# Sheet1.net
KiCad netlist of a schematic drawn in Altium Designer
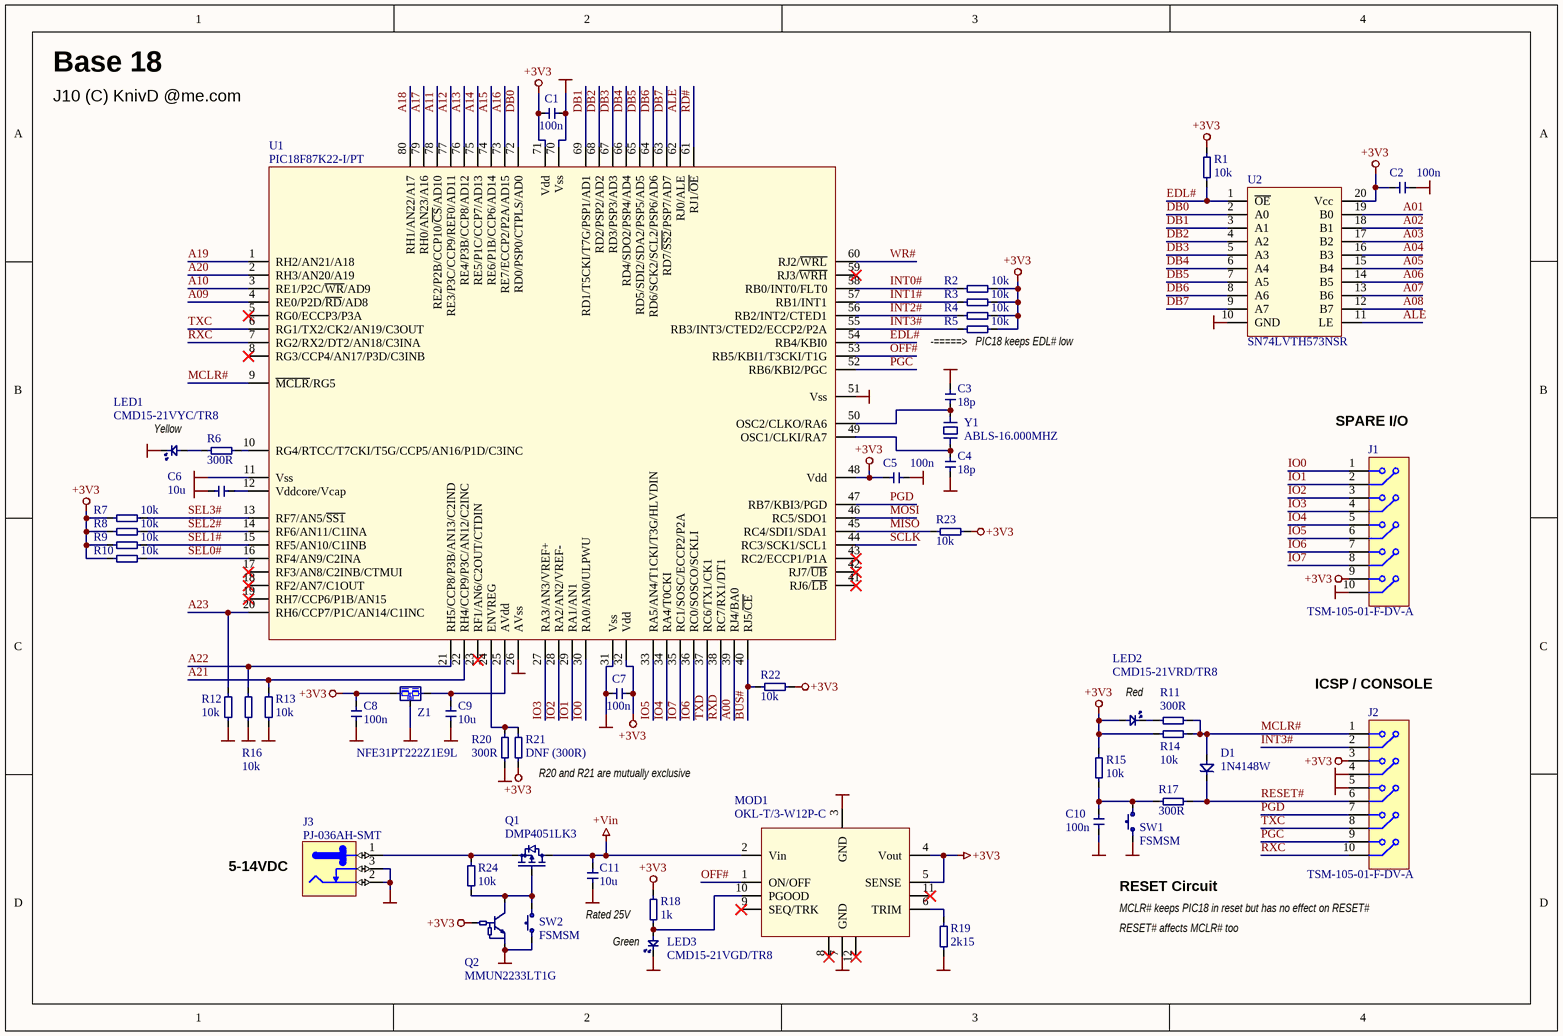
[diagram p0: Sheet1.SchDoc]

(export (version "E")
  (design (tool "Eeschema 10.0.6"))
  (components
    (comp (ref "C1")
      (value "100n")
      (footprint "CAPC3216X110N")
      (description "Capacitor")
      (libsource (lib "Discretes") (part "Capacitor"))
    )
    (comp (ref "C2")
      (value "100n")
      (footprint "CAPC3216X110N")
      (description "Capacitor")
      (libsource (lib "Discretes") (part "Capacitor"))
    )
    (comp (ref "C3")
      (value "18p")
      (footprint "CAPC3216X110N")
      (description "Capacitor")
      (libsource (lib "Discretes") (part "Capacitor"))
    )
    (comp (ref "C4")
      (value "18p")
      (footprint "CAPC3216X110N")
      (description "Capacitor")
      (libsource (lib "Discretes") (part "Capacitor"))
    )
    (comp (ref "C5")
      (value "100n")
      (footprint "CAPC3216X110N")
      (description "Capacitor")
      (libsource (lib "Discretes") (part "Capacitor"))
    )
    (comp (ref "C6")
      (value "10u")
      (footprint "CAPC3216X110N")
      (description "Capacitor")
      (libsource (lib "Discretes") (part "Capacitor"))
    )
    (comp (ref "C7")
      (value "100n")
      (footprint "CAPC3216X110N")
      (description "Capacitor")
      (libsource (lib "Discretes") (part "Capacitor"))
    )
    (comp (ref "C8")
      (value "100n")
      (footprint "CAPC3216X110N")
      (description "Capacitor")
      (libsource (lib "Discretes") (part "Capacitor"))
    )
    (comp (ref "C9")
      (value "10u")
      (footprint "CAPC3216X110N")
      (description "Capacitor")
      (libsource (lib "Discretes") (part "Capacitor"))
    )
    (comp (ref "C10")
      (value "100n")
      (footprint "CAPC3216X110N")
      (description "Capacitor")
      (libsource (lib "Discretes") (part "Capacitor"))
    )
    (comp (ref "C11")
      (value "10u/25V")
      (footprint "CAPC3216X110N")
      (description "Capacitor")
      (fields (field (name "NOTE") "10u"))
      (libsource (lib "Discretes") (part "Capacitor"))
    )
    (comp (ref "D1")
      (value "1N4148W")
      (footprint "SOD-123")
      (description "Schottky diode")
      (libsource (lib "Discretes") (part "Diode Schottky"))
    )
    (comp (ref "J1")
      (value "TSM-105-01-F-DV-A")
      (footprint "2015-2X05XD")
      (description "Dual row, 10-way connector")
      (libsource (lib "Connectors") (part "Connector 2x5"))
    )
    (comp (ref "J2")
      (value "TSM-105-01-F-DV-A")
      (footprint "2015-2X05XD")
      (description "Dual row, 10-way connector")
      (libsource (lib "Connectors") (part "Connector 2x5"))
    )
    (comp (ref "J3")
      (value "PJ-036AH-SMT")
      (footprint "PJ-036AH-SMT")
      (description "2.1/5.5mm barrel power jack, SMT")
      (fields (field (name "AUTHOR") "CERN DEM JLC"))
      (libsource (lib "Connectors") (part "LUMBERG_161314"))
    )
    (comp (ref "LED1")
      (value "CMD15-21VYC/TR8")
      (footprint "LED_OSRAM_LYN971")
      (description "Light Emitting Diode")
      (libsource (lib "Discretes") (part "LED"))
    )
    (comp (ref "LED2")
      (value "CMD15-21VRD/TR8")
      (footprint "LED_OSRAM_LHN974")
      (description "Light Emitting Diode")
      (libsource (lib "") (part "LED_1"))
    )
    (comp (ref "LED3")
      (value "CMD15-21VGD/TR8")
      (footprint "LED_OSRAM_LGN971")
      (description "Light Emitting Diode")
      (libsource (lib "Discretes") (part "LED"))
    )
    (comp (ref "MOD1")
      (value "OKL-T/3-W12P-C")
      (footprint "OKL-T/3-W12")
      (description "Programmable Output 3-Amp iLGA SMT PoLs")
      (fields (field (name "MANUFACTURER") "Murata"))
      (libsource (lib "Modules") (part "OKL-T/3-W12"))
    )
    (comp (ref "Q1")
      (value "DMP4051LK3")
      (footprint "TO228P991X239-3N-R546X521")
      (description "P-channel FET transistor")
      (libsource (lib "Discretes") (part "P-FET"))
    )
    (comp (ref "Q2")
      (value "MMUN2233LT1G")
      (footprint "SOT23-3")
      (description "NPN biased bipolar transistor")
      (libsource (lib "Discretes") (part "NPN BIASED"))
    )
    (comp (ref "R1")
      (value "10k")
      (footprint "RESC3216X75N")
      (description "Resistor")
      (libsource (lib "") (part "Resistor_1"))
    )
    (comp (ref "R2")
      (value "10k")
      (footprint "RESC3216X75N")
      (description "Resistor")
      (libsource (lib "") (part "Resistor_2"))
    )
    (comp (ref "R3")
      (value "10k")
      (footprint "RESC3216X75N")
      (description "Resistor")
      (libsource (lib "") (part "Resistor_2"))
    )
    (comp (ref "R4")
      (value "10k")
      (footprint "RESC3216X75N")
      (description "Resistor")
      (libsource (lib "") (part "Resistor_2"))
    )
    (comp (ref "R5")
      (value "10k")
      (footprint "RESC3216X75N")
      (description "Resistor")
      (libsource (lib "") (part "Resistor_2"))
    )
    (comp (ref "R6")
      (value "300R")
      (footprint "RESC3216X75N")
      (description "Resistor")
      (libsource (lib "") (part "Resistor_3"))
    )
    (comp (ref "R7")
      (value "10k")
      (footprint "RESC3216X75N")
      (description "Resistor")
      (libsource (lib "") (part "Resistor_1"))
    )
    (comp (ref "R8")
      (value "10k")
      (footprint "RESC3216X75N")
      (description "Resistor")
      (libsource (lib "") (part "Resistor_1"))
    )
    (comp (ref "R9")
      (value "10k")
      (footprint "RESC3216X75N")
      (description "Resistor")
      (libsource (lib "") (part "Resistor_1"))
    )
    (comp (ref "R10")
      (value "10k")
      (footprint "RESC3216X75N")
      (description "Resistor")
      (libsource (lib "") (part "Resistor_1"))
    )
    (comp (ref "R11")
      (value "300R")
      (footprint "RESC3216X75N")
      (description "Resistor")
      (libsource (lib "") (part "Resistor_2"))
    )
    (comp (ref "R12")
      (value "10k")
      (footprint "RESC3216X75N")
      (description "Resistor")
      (libsource (lib "Discretes") (part "Resistor"))
    )
    (comp (ref "R13")
      (value "10k")
      (footprint "RESC3216X75N")
      (description "Resistor")
      (libsource (lib "Discretes") (part "Resistor"))
    )
    (comp (ref "R14")
      (value "10k")
      (footprint "RESC3216X75N")
      (description "Resistor")
      (libsource (lib "") (part "Resistor_2"))
    )
    (comp (ref "R15")
      (value "10k")
      (footprint "RESC3216X75N")
      (description "Resistor")
      (libsource (lib "") (part "Resistor_1"))
    )
    (comp (ref "R16")
      (value "10k")
      (footprint "RESC3216X75N")
      (description "Resistor")
      (libsource (lib "Discretes") (part "Resistor"))
    )
    (comp (ref "R17")
      (value "300R")
      (footprint "RESC3216X75N")
      (description "Resistor")
      (libsource (lib "") (part "Resistor_3"))
    )
    (comp (ref "R18")
      (value "1k")
      (footprint "RESC3216X75N")
      (description "Resistor")
      (libsource (lib "Discretes") (part "Resistor"))
    )
    (comp (ref "R19")
      (value "2k15")
      (footprint "RESC3216X75N")
      (description "Resistor")
      (libsource (lib "") (part "Resistor_1"))
    )
    (comp (ref "R20")
      (value "300R")
      (footprint "RESC3216X75N")
      (description "Resistor")
      (libsource (lib "Discretes") (part "Resistor"))
    )
    (comp (ref "R21")
      (value "DNF (300R)")
      (footprint "RESC3216X75N")
      (description "Resistor")
      (libsource (lib "Discretes") (part "Resistor"))
    )
    (comp (ref "R22")
      (value "10k")
      (footprint "RESC3216X75N")
      (description "Resistor")
      (libsource (lib "") (part "Resistor_2"))
    )
    (comp (ref "R23")
      (value "10k")
      (footprint "RESC3216X75N")
      (description "Resistor")
      (libsource (lib "") (part "Resistor_2"))
    )
    (comp (ref "R24")
      (value "10k")
      (footprint "RESC3216X75N")
      (description "Resistor")
      (libsource (lib "") (part "Resistor_1"))
    )
    (comp (ref "SW1")
      (value "FSMSM")
      (footprint "PB_TYCO_FSMSM")
      (description "Switch, Momentary, Normal Open")
      (libsource (lib "Switches") (part "Switch MNO SPST"))
    )
    (comp (ref "SW2")
      (value "FSMSM")
      (footprint "PB_TYCO_FSMSM")
      (description "Switch, Momentary, Normal Open")
      (libsource (lib "Switches") (part "Switch MNO SPST"))
    )
    (comp (ref "U1")
      (value "PIC18F87K22-I/PT")
      (footprint "QFP50P1400X1400X120-80N")
      (description "High-Performance, 1-Mbit Enhanced Flash MCUs  with 12-Bit A/D and XLP Technology")
      (fields (field (name "MANUFACTURER") "Microchip"))
      (libsource (lib "IC Microcontrollers and Processors") (part "PIC18F87K22"))
    )
    (comp (ref "U2")
      (value "SN74LVTH573NSR")
      (footprint "SOIC127P780X200-20N")
      (description "A Octal Transparent D-Type Latches With 3-State Outputs")
      (libsource (lib "IC Logic") (part "74xxx373"))
    )
    (comp (ref "Y1")
      (value "ABLS-16.000MHZ")
      (footprint "XTAL1140X470X160N")
      (description "Crystal Resonator")
      (libsource (lib "Discretes") (part "Crystal"))
    )
    (comp (ref "Z1")
      (value "NFE31PT222Z1E9L")
      (footprint "NFE31xx")
      (description "Hybrid filter")
      (libsource (lib "Misc") (part "Filter"))
    )
  )
  (nets
    (net (code "1") (name "+3V3") (class "Default")
      (node (ref "C1") (pin "1") (pintype "passive"))
      (node (ref "C2") (pin "1") (pintype "passive"))
      (node (ref "C5") (pin "1") (pintype "passive"))
      (node (ref "C7") (pin "1") (pintype "passive"))
      (node (ref "C8") (pin "1") (pintype "passive"))
      (node (ref "J1") (pin "9") (pinfunction "9_9") (pintype "passive"))
      (node (ref "J2") (pin "3") (pinfunction "3_3") (pintype "passive"))
      (node (ref "LED2") (pin "2") (pintype "passive"))
      (node (ref "MOD1") (pin "4") (pinfunction "Vout_4") (pintype "passive"))
      (node (ref "MOD1") (pin "5") (pinfunction "SENSE_5") (pintype "passive"))
      (node (ref "Q2") (pin "1") (pinfunction "B_1") (pintype "passive"))
      (node (ref "R1") (pin "2") (pintype "passive"))
      (node (ref "R10") (pin "1") (pintype "passive"))
      (node (ref "R14") (pin "2") (pintype "passive"))
      (node (ref "R15") (pin "2") (pintype "passive"))
      (node (ref "R18") (pin "1") (pintype "passive"))
      (node (ref "R2") (pin "1") (pintype "passive"))
      (node (ref "R21") (pin "2") (pintype "passive"))
      (node (ref "R22") (pin "1") (pintype "passive"))
      (node (ref "R23") (pin "1") (pintype "passive"))
      (node (ref "R3") (pin "1") (pintype "passive"))
      (node (ref "R4") (pin "1") (pintype "passive"))
      (node (ref "R5") (pin "1") (pintype "passive"))
      (node (ref "R7") (pin "1") (pintype "passive"))
      (node (ref "R8") (pin "1") (pintype "passive"))
      (node (ref "R9") (pin "1") (pintype "passive"))
      (node (ref "U1") (pin "32") (pinfunction "Vdd_32") (pintype "passive"))
      (node (ref "U1") (pin "48") (pinfunction "Vdd_48") (pintype "passive"))
      (node (ref "U1") (pin "71") (pinfunction "Vdd_71") (pintype "passive"))
      (node (ref "U2") (pin "20") (pinfunction "Vcc_20") (pintype "passive"))
      (node (ref "Z1") (pin "1") (pintype "passive"))
    )
    (net (code "2") (name "+Vin") (class "Default")
      (node (ref "C11") (pin "1") (pintype "passive"))
      (node (ref "MOD1") (pin "2") (pinfunction "Vin_2") (pintype "passive"))
      (node (ref "Q1") (pin "3") (pinfunction "D_3") (pintype "passive"))
    )
    (net (code "3") (name "/A00") (class "Default")
      (node (ref "U1") (pin "39") (pinfunction "RJ4/BA0_39") (pintype "passive"))
    )
    (net (code "4") (name "/A01") (class "Default")
      (node (ref "U2") (pin "19") (pinfunction "B0_19") (pintype "passive"))
    )
    (net (code "5") (name "/A02") (class "Default")
      (node (ref "U2") (pin "18") (pinfunction "B1_18") (pintype "passive"))
    )
    (net (code "6") (name "/A03") (class "Default")
      (node (ref "U2") (pin "17") (pinfunction "B2_17") (pintype "passive"))
    )
    (net (code "7") (name "/A04") (class "Default")
      (node (ref "U2") (pin "16") (pinfunction "B3_16") (pintype "passive"))
    )
    (net (code "8") (name "/A05") (class "Default")
      (node (ref "U2") (pin "15") (pinfunction "B4_15") (pintype "passive"))
    )
    (net (code "9") (name "/A06") (class "Default")
      (node (ref "U2") (pin "14") (pinfunction "B5_14") (pintype "passive"))
    )
    (net (code "10") (name "/A07") (class "Default")
      (node (ref "U2") (pin "13") (pinfunction "B6_13") (pintype "passive"))
    )
    (net (code "11") (name "/A08") (class "Default")
      (node (ref "U2") (pin "12") (pinfunction "B7_12") (pintype "passive"))
    )
    (net (code "12") (name "/A09") (class "Default")
      (node (ref "U1") (pin "4") (pinfunction "RE0/P2D/~{RD}/AD8_4") (pintype "passive"))
    )
    (net (code "13") (name "/A10") (class "Default")
      (node (ref "U1") (pin "3") (pinfunction "RE1/P2C/~{WR}/AD9_3") (pintype "passive"))
    )
    (net (code "14") (name "/A11") (class "Default")
      (node (ref "U1") (pin "78") (pinfunction "RE2/P2B/CCP10/~{CS}/AD10_78") (pintype "passive"))
    )
    (net (code "15") (name "/A12") (class "Default")
      (node (ref "U1") (pin "77") (pinfunction "RE3/P3C/CCP9/REF0/AD11_77") (pintype "passive"))
    )
    (net (code "16") (name "/A13") (class "Default")
      (node (ref "U1") (pin "76") (pinfunction "RE4/P3B/CCP8/AD12_76") (pintype "passive"))
    )
    (net (code "17") (name "/A14") (class "Default")
      (node (ref "U1") (pin "75") (pinfunction "RE5/P1C/CCP7/AD13_75") (pintype "passive"))
    )
    (net (code "18") (name "/A15") (class "Default")
      (node (ref "U1") (pin "74") (pinfunction "RE6/P1B/CCP6/AD14_74") (pintype "passive"))
    )
    (net (code "19") (name "/A16") (class "Default")
      (node (ref "U1") (pin "73") (pinfunction "RE7/ECCP2/P2A/AD15_73") (pintype "passive"))
    )
    (net (code "20") (name "/A17") (class "Default")
      (node (ref "U1") (pin "79") (pinfunction "RH0/AN23/A16_79") (pintype "passive"))
    )
    (net (code "21") (name "/A18") (class "Default")
      (node (ref "U1") (pin "80") (pinfunction "RH1/AN22/A17_80") (pintype "passive"))
    )
    (net (code "22") (name "/A19") (class "Default")
      (node (ref "U1") (pin "1") (pinfunction "RH2/AN21/A18_1") (pintype "passive"))
    )
    (net (code "23") (name "/A20") (class "Default")
      (node (ref "U1") (pin "2") (pinfunction "RH3/AN20/A19_2") (pintype "passive"))
    )
    (net (code "24") (name "/A21") (class "Default")
      (node (ref "R13") (pin "1") (pintype "passive"))
      (node (ref "U1") (pin "22") (pinfunction "RH4/CCP9/P3C/AN12/C2INC_22") (pintype "passive"))
    )
    (net (code "25") (name "/A22") (class "Default")
      (node (ref "R16") (pin "1") (pintype "passive"))
      (node (ref "U1") (pin "21") (pinfunction "RH5/CCP8/P3B/AN13/C2IND_21") (pintype "passive"))
    )
    (net (code "26") (name "/A23") (class "Default")
      (node (ref "R12") (pin "1") (pintype "passive"))
      (node (ref "U1") (pin "20") (pinfunction "RH6/CCP7/P1C/AN14/C1INC_20") (pintype "passive"))
    )
    (net (code "27") (name "/ALE") (class "Default")
      (node (ref "U1") (pin "62") (pinfunction "RJ0/ALE_62") (pintype "passive"))
      (node (ref "U2") (pin "11") (pinfunction "LE_11") (pintype "passive"))
    )
    (net (code "28") (name "/BUS#") (class "Default")
      (node (ref "R22") (pin "2") (pintype "passive"))
      (node (ref "U1") (pin "40") (pinfunction "RJ5/~{CE}_40") (pintype "passive"))
    )
    (net (code "29") (name "/DB0") (class "Default")
      (node (ref "U1") (pin "72") (pinfunction "RD0/PSP0/CTPLS/AD0_72") (pintype "passive"))
      (node (ref "U2") (pin "2") (pinfunction "A0_2") (pintype "passive"))
    )
    (net (code "30") (name "/DB1") (class "Default")
      (node (ref "U1") (pin "69") (pinfunction "RD1/T5CKI/T7G/PSP1/AD1_69") (pintype "passive"))
      (node (ref "U2") (pin "3") (pinfunction "A1_3") (pintype "passive"))
    )
    (net (code "31") (name "/DB2") (class "Default")
      (node (ref "U1") (pin "68") (pinfunction "RD2/PSP2/AD2_68") (pintype "passive"))
      (node (ref "U2") (pin "4") (pinfunction "A2_4") (pintype "passive"))
    )
    (net (code "32") (name "/DB3") (class "Default")
      (node (ref "U1") (pin "67") (pinfunction "RD3/PSP3/AD3_67") (pintype "passive"))
      (node (ref "U2") (pin "5") (pinfunction "A3_5") (pintype "passive"))
    )
    (net (code "33") (name "/DB4") (class "Default")
      (node (ref "U1") (pin "66") (pinfunction "RD4/SDO2/PSP4/AD4_66") (pintype "passive"))
      (node (ref "U2") (pin "6") (pinfunction "A4_6") (pintype "passive"))
    )
    (net (code "34") (name "/DB5") (class "Default")
      (node (ref "U1") (pin "65") (pinfunction "RD5/SDI2/SDA2/PSP5/AD5_65") (pintype "passive"))
      (node (ref "U2") (pin "7") (pinfunction "A5_7") (pintype "passive"))
    )
    (net (code "35") (name "/DB6") (class "Default")
      (node (ref "U1") (pin "64") (pinfunction "RD6/SCK2/SCL2/PSP6/AD6_64") (pintype "passive"))
      (node (ref "U2") (pin "8") (pinfunction "A6_8") (pintype "passive"))
    )
    (net (code "36") (name "/DB7") (class "Default")
      (node (ref "U1") (pin "63") (pinfunction "RD7/~{SS2}/PSP7/AD7_63") (pintype "passive"))
      (node (ref "U2") (pin "9") (pinfunction "A7_9") (pintype "passive"))
    )
    (net (code "37") (name "/EDL#") (class "Default")
      (node (ref "R1") (pin "1") (pintype "passive"))
      (node (ref "U1") (pin "54") (pinfunction "RB4/KBI0_54") (pintype "passive"))
      (node (ref "U2") (pin "1") (pinfunction "~{OE}_1") (pintype "passive"))
    )
    (net (code "38") (name "/INT0#") (class "Default")
      (node (ref "R2") (pin "2") (pintype "passive"))
      (node (ref "U1") (pin "58") (pinfunction "RB0/INT0/FLT0_58") (pintype "passive"))
    )
    (net (code "39") (name "/INT1#") (class "Default")
      (node (ref "R3") (pin "2") (pintype "passive"))
      (node (ref "U1") (pin "57") (pinfunction "RB1/INT1_57") (pintype "passive"))
    )
    (net (code "40") (name "/INT2#") (class "Default")
      (node (ref "R4") (pin "2") (pintype "passive"))
      (node (ref "U1") (pin "56") (pinfunction "RB2/INT2/CTED1_56") (pintype "passive"))
    )
    (net (code "41") (name "/INT3#") (class "Default")
      (node (ref "J2") (pin "2") (pinfunction "2_2") (pintype "passive"))
      (node (ref "R5") (pin "2") (pintype "passive"))
      (node (ref "U1") (pin "55") (pinfunction "RB3/INT3/CTED2/ECCP2/P2A_55") (pintype "passive"))
    )
    (net (code "42") (name "/IO0") (class "Default")
      (node (ref "J1") (pin "1") (pinfunction "1_1") (pintype "passive"))
      (node (ref "U1") (pin "30") (pinfunction "RA0/AN0/ULPWU_30") (pintype "passive"))
    )
    (net (code "43") (name "/IO1") (class "Default")
      (node (ref "J1") (pin "2") (pinfunction "2_2") (pintype "passive"))
      (node (ref "U1") (pin "29") (pinfunction "RA1/AN1_29") (pintype "passive"))
    )
    (net (code "44") (name "/IO2") (class "Default")
      (node (ref "J1") (pin "3") (pinfunction "3_3") (pintype "passive"))
      (node (ref "U1") (pin "28") (pinfunction "RA2/AN2/VREF-_28") (pintype "passive"))
    )
    (net (code "45") (name "/IO3") (class "Default")
      (node (ref "J1") (pin "4") (pinfunction "4_4") (pintype "passive"))
      (node (ref "U1") (pin "27") (pinfunction "RA3/AN3/VREF+_27") (pintype "passive"))
    )
    (net (code "46") (name "/IO4") (class "Default")
      (node (ref "J1") (pin "5") (pinfunction "5_5") (pintype "passive"))
      (node (ref "U1") (pin "34") (pinfunction "RA4/T0CKI_34") (pintype "passive"))
    )
    (net (code "47") (name "/IO5") (class "Default")
      (node (ref "J1") (pin "6") (pinfunction "6_6") (pintype "passive"))
      (node (ref "U1") (pin "33") (pinfunction "RA5/AN4/T1CKI/T3G/HLVDIN_33") (pintype "passive"))
    )
    (net (code "48") (name "/IO6") (class "Default")
      (node (ref "J1") (pin "7") (pinfunction "7_7") (pintype "passive"))
      (node (ref "U1") (pin "36") (pinfunction "RC0/SOSCO/SCKLI_36") (pintype "passive"))
    )
    (net (code "49") (name "/IO7") (class "Default")
      (node (ref "J1") (pin "8") (pinfunction "8_8") (pintype "passive"))
      (node (ref "U1") (pin "35") (pinfunction "RC1/SOSC/ECCP2/P2A_35") (pintype "passive"))
    )
    (net (code "50") (name "/MCLR#") (class "Default")
      (node (ref "D1") (pin "2") (pintype "passive"))
      (node (ref "J2") (pin "1") (pinfunction "1_1") (pintype "passive"))
      (node (ref "R11") (pin "1") (pintype "passive"))
      (node (ref "R14") (pin "1") (pintype "passive"))
      (node (ref "U1") (pin "9") (pinfunction "~{MCLR}/RG5_9") (pintype "passive"))
    )
    (net (code "51") (name "/MISO") (class "Default")
      (node (ref "R23") (pin "2") (pintype "passive"))
      (node (ref "U1") (pin "45") (pinfunction "RC4/SDI1/SDA1_45") (pintype "passive"))
    )
    (net (code "52") (name "/MOSI") (class "Default")
      (node (ref "U1") (pin "46") (pinfunction "RC5/SDO1_46") (pintype "passive"))
    )
    (net (code "53") (name "/OFF#") (class "Default")
      (node (ref "MOD1") (pin "1") (pinfunction "ON/OFF_1") (pintype "passive"))
      (node (ref "U1") (pin "53") (pinfunction "RB5/KBI1/T3CKI/T1G_53") (pintype "passive"))
    )
    (net (code "54") (name "/PGC") (class "Default")
      (node (ref "J2") (pin "9") (pinfunction "9_9") (pintype "passive"))
      (node (ref "U1") (pin "52") (pinfunction "RB6/KBI2/PGC_52") (pintype "passive"))
    )
    (net (code "55") (name "/PGD") (class "Default")
      (node (ref "J2") (pin "7") (pinfunction "7_7") (pintype "passive"))
      (node (ref "U1") (pin "47") (pinfunction "RB7/KBI3/PGD_47") (pintype "passive"))
    )
    (net (code "56") (name "/RD#") (class "Default")
      (node (ref "U1") (pin "61") (pinfunction "RJ1/~{OE}_61") (pintype "passive"))
    )
    (net (code "57") (name "/RESET#") (class "Default")
      (node (ref "D1") (pin "1") (pintype "passive"))
      (node (ref "J2") (pin "6") (pinfunction "6_6") (pintype "passive"))
      (node (ref "R17") (pin "2") (pintype "passive"))
    )
    (net (code "58") (name "/RXC") (class "Default")
      (node (ref "J2") (pin "10") (pinfunction "10_10") (pintype "passive"))
      (node (ref "U1") (pin "7") (pinfunction "RG2/RX2/DT2/AN18/C3INA_7") (pintype "passive"))
    )
    (net (code "59") (name "/RXD") (class "Default")
      (node (ref "U1") (pin "38") (pinfunction "RC7/RX1/DT1_38") (pintype "passive"))
    )
    (net (code "60") (name "/SCLK") (class "Default")
      (node (ref "U1") (pin "44") (pinfunction "RC3/SCK1/SCL1_44") (pintype "passive"))
    )
    (net (code "61") (name "/SEL0#") (class "Default")
      (node (ref "R10") (pin "2") (pintype "passive"))
      (node (ref "U1") (pin "16") (pinfunction "RF4/AN9/C2INA_16") (pintype "passive"))
    )
    (net (code "62") (name "/SEL1#") (class "Default")
      (node (ref "R9") (pin "2") (pintype "passive"))
      (node (ref "U1") (pin "15") (pinfunction "RF5/AN10/C1INB_15") (pintype "passive"))
    )
    (net (code "63") (name "/SEL2#") (class "Default")
      (node (ref "R8") (pin "2") (pintype "passive"))
      (node (ref "U1") (pin "14") (pinfunction "RF6/AN11/C1INA_14") (pintype "passive"))
    )
    (net (code "64") (name "/SEL3#") (class "Default")
      (node (ref "R7") (pin "2") (pintype "passive"))
      (node (ref "U1") (pin "13") (pinfunction "RF7/AN5/~{SS1}_13") (pintype "passive"))
    )
    (net (code "65") (name "/TXC") (class "Default")
      (node (ref "J2") (pin "8") (pinfunction "8_8") (pintype "passive"))
      (node (ref "U1") (pin "6") (pinfunction "RG1/TX2/CK2/AN19/C3OUT_6") (pintype "passive"))
    )
    (net (code "66") (name "/TXD") (class "Default")
      (node (ref "U1") (pin "37") (pinfunction "RC6/TX1/CK1_37") (pintype "passive"))
    )
    (net (code "67") (name "/WR#") (class "Default")
      (node (ref "U1") (pin "60") (pinfunction "RJ2/~{WRL}_60") (pintype "passive"))
    )
    (net (code "68") (name "GND") (class "Default")
      (node (ref "C1") (pin "2") (pintype "passive"))
      (node (ref "C10") (pin "1") (pintype "passive"))
      (node (ref "C11") (pin "2") (pintype "passive"))
      (node (ref "C2") (pin "2") (pintype "passive"))
      (node (ref "C3") (pin "2") (pintype "passive"))
      (node (ref "C4") (pin "1") (pintype "passive"))
      (node (ref "C5") (pin "2") (pintype "passive"))
      (node (ref "C6") (pin "2") (pintype "passive"))
      (node (ref "C7") (pin "2") (pintype "passive"))
      (node (ref "C8") (pin "2") (pintype "passive"))
      (node (ref "C9") (pin "2") (pintype "passive"))
      (node (ref "J1") (pin "10") (pinfunction "10_10") (pintype "passive"))
      (node (ref "J2") (pin "4") (pinfunction "4_4") (pintype "passive"))
      (node (ref "J2") (pin "5") (pinfunction "5_5") (pintype "passive"))
      (node (ref "J3") (pin "2") (pintype "bidirectional"))
      (node (ref "J3") (pin "3") (pintype "bidirectional"))
      (node (ref "LED1") (pin "1") (pintype "passive"))
      (node (ref "LED3") (pin "1") (pintype "passive"))
      (node (ref "MOD1") (pin "3") (pinfunction "GND_3") (pintype "passive"))
      (node (ref "MOD1") (pin "7") (pinfunction "GND_7") (pintype "passive"))
      (node (ref "Q2") (pin "2") (pinfunction "E_2") (pintype "passive"))
      (node (ref "R12") (pin "2") (pintype "passive"))
      (node (ref "R13") (pin "2") (pintype "passive"))
      (node (ref "R16") (pin "2") (pintype "passive"))
      (node (ref "R19") (pin "1") (pintype "passive"))
      (node (ref "R20") (pin "2") (pintype "passive"))
      (node (ref "SW1") (pin "1") (pintype "passive"))
      (node (ref "SW2") (pin "1") (pintype "passive"))
      (node (ref "U1") (pin "11") (pinfunction "Vss_11") (pintype "passive"))
      (node (ref "U1") (pin "26") (pinfunction "AVss_26") (pintype "passive"))
      (node (ref "U1") (pin "31") (pinfunction "Vss_31") (pintype "passive"))
      (node (ref "U1") (pin "51") (pinfunction "Vss_51") (pintype "passive"))
      (node (ref "U1") (pin "70") (pinfunction "Vss_70") (pintype "passive"))
      (node (ref "U2") (pin "10") (pinfunction "GND_10") (pintype "passive"))
      (node (ref "Z1") (pin "2") (pintype "passive"))
    )
    (net (code "69") (name "Net-(C10-Pad2)") (class "Default")
      (node (ref "C10") (pin "2") (pintype "passive"))
      (node (ref "R15") (pin "1") (pintype "passive"))
      (node (ref "R17") (pin "1") (pintype "passive"))
      (node (ref "SW1") (pin "2") (pintype "passive"))
    )
    (net (code "70") (name "Net-(LED1-Pad2)") (class "Default")
      (node (ref "LED1") (pin "2") (pintype "passive"))
      (node (ref "R6") (pin "1") (pintype "passive"))
    )
    (net (code "71") (name "Net-(LED2-Pad1)") (class "Default")
      (node (ref "LED2") (pin "1") (pintype "passive"))
      (node (ref "R11") (pin "2") (pintype "passive"))
    )
    (net (code "72") (name "Net-(MOD1-PGOOD)") (class "Default")
      (node (ref "LED3") (pin "2") (pintype "passive"))
      (node (ref "MOD1") (pin "10") (pinfunction "PGOOD_10") (pintype "passive"))
      (node (ref "R18") (pin "2") (pintype "passive"))
    )
    (net (code "73") (name "Net-(MOD1-TRIM)") (class "Default")
      (node (ref "MOD1") (pin "6") (pinfunction "TRIM_6") (pintype "passive"))
      (node (ref "R19") (pin "2") (pintype "passive"))
    )
    (net (code "74") (name "Net-(Q1-G)") (class "Default")
      (node (ref "Q1") (pin "1") (pinfunction "G_1") (pintype "passive"))
      (node (ref "Q2") (pin "3") (pinfunction "C_3") (pintype "passive"))
      (node (ref "R24") (pin "1") (pintype "passive"))
      (node (ref "SW2") (pin "2") (pintype "passive"))
    )
    (net (code "75") (name "Net-(Q1-S)") (class "Default")
      (node (ref "J3") (pin "1") (pintype "bidirectional"))
      (node (ref "Q1") (pin "2") (pinfunction "S_2") (pintype "passive"))
      (node (ref "R24") (pin "2") (pintype "passive"))
    )
    (net (code "76") (name "Net-(U1-AVdd)") (class "Default")
      (node (ref "C9") (pin "1") (pintype "passive"))
      (node (ref "U1") (pin "25") (pinfunction "AVdd_25") (pintype "passive"))
      (node (ref "Z1") (pin "3") (pintype "passive"))
    )
    (net (code "77") (name "Net-(U1-ENVREG)") (class "Default")
      (node (ref "R20") (pin "1") (pintype "passive"))
      (node (ref "R21") (pin "1") (pintype "passive"))
      (node (ref "U1") (pin "24") (pinfunction "ENVREG_24") (pintype "passive"))
    )
    (net (code "78") (name "Net-(U1-OSC1{slash}CLKI{slash}RA7)") (class "Default")
      (node (ref "C4") (pin "2") (pintype "passive"))
      (node (ref "U1") (pin "49") (pinfunction "OSC1/CLKI/RA7_49") (pintype "passive"))
      (node (ref "Y1") (pin "1") (pintype "passive"))
    )
    (net (code "79") (name "Net-(U1-OSC2{slash}CLKO{slash}RA6)") (class "Default")
      (node (ref "C3") (pin "1") (pintype "passive"))
      (node (ref "U1") (pin "50") (pinfunction "OSC2/CLKO/RA6_50") (pintype "passive"))
      (node (ref "Y1") (pin "2") (pintype "passive"))
    )
    (net (code "80") (name "Net-(U1-RG4{slash}RTCC{slash}T7CKI{slash}T5G{slash}CCP5{slash}AN16{slash}P1D{slash}C3INC)") (class "Default")
      (node (ref "R6") (pin "2") (pintype "passive"))
      (node (ref "U1") (pin "10") (pinfunction "RG4/RTCC/T7CKI/T5G/CCP5/AN16/P1D/C3INC_10") (pintype "passive"))
    )
    (net (code "81") (name "Net-(U1-Vddcore{slash}Vcap)") (class "Default")
      (node (ref "C6") (pin "1") (pintype "passive"))
      (node (ref "U1") (pin "12") (pinfunction "Vddcore/Vcap_12") (pintype "passive"))
    )
    (net (code "82") (name "unconnected-(MOD1-Pad8)") (class "Default")
      (node (ref "MOD1") (pin "8") (pintype "passive+no_connect"))
    )
    (net (code "83") (name "unconnected-(MOD1-Pad11)") (class "Default")
      (node (ref "MOD1") (pin "11") (pintype "passive+no_connect"))
    )
    (net (code "84") (name "unconnected-(MOD1-Pad12)") (class "Default")
      (node (ref "MOD1") (pin "12") (pintype "passive+no_connect"))
    )
    (net (code "85") (name "unconnected-(MOD1-SEQ{slash}TRK-Pad9)") (class "Default")
      (node (ref "MOD1") (pin "9") (pinfunction "SEQ/TRK_9") (pintype "passive+no_connect"))
    )
    (net (code "86") (name "unconnected-(U1-RC2{slash}ECCP1{slash}P1A-Pad43)") (class "Default")
      (node (ref "U1") (pin "43") (pinfunction "RC2/ECCP1/P1A_43") (pintype "passive+no_connect"))
    )
    (net (code "87") (name "unconnected-(U1-RF1{slash}AN6{slash}C2OUT{slash}CTDIN-Pad23)") (class "Default")
      (node (ref "U1") (pin "23") (pinfunction "RF1/AN6/C2OUT/CTDIN_23") (pintype "passive+no_connect"))
    )
    (net (code "88") (name "unconnected-(U1-RF2{slash}AN7{slash}C1OUT-Pad18)") (class "Default")
      (node (ref "U1") (pin "18") (pinfunction "RF2/AN7/C1OUT_18") (pintype "passive+no_connect"))
    )
    (net (code "89") (name "unconnected-(U1-RF3{slash}AN8{slash}C2INB{slash}CTMUI-Pad17)") (class "Default")
      (node (ref "U1") (pin "17") (pinfunction "RF3/AN8/C2INB/CTMUI_17") (pintype "passive+no_connect"))
    )
    (net (code "90") (name "unconnected-(U1-RG0{slash}ECCP3{slash}P3A-Pad5)") (class "Default")
      (node (ref "U1") (pin "5") (pinfunction "RG0/ECCP3/P3A_5") (pintype "passive+no_connect"))
    )
    (net (code "91") (name "unconnected-(U1-RG3{slash}CCP4{slash}AN17{slash}P3D{slash}C3INB-Pad8)") (class "Default")
      (node (ref "U1") (pin "8") (pinfunction "RG3/CCP4/AN17/P3D/C3INB_8") (pintype "passive+no_connect"))
    )
    (net (code "92") (name "unconnected-(U1-RH7{slash}CCP6{slash}P1B{slash}AN15-Pad19)") (class "Default")
      (node (ref "U1") (pin "19") (pinfunction "RH7/CCP6/P1B/AN15_19") (pintype "passive+no_connect"))
    )
    (net (code "93") (name "unconnected-(U1-RJ3{slash}~{WRH}-Pad59)") (class "Default")
      (node (ref "U1") (pin "59") (pinfunction "RJ3/~{WRH}_59") (pintype "passive+no_connect"))
    )
    (net (code "94") (name "unconnected-(U1-RJ6{slash}~{LB}-Pad41)") (class "Default")
      (node (ref "U1") (pin "41") (pinfunction "RJ6/~{LB}_41") (pintype "passive+no_connect"))
    )
    (net (code "95") (name "unconnected-(U1-RJ7{slash}~{UB}-Pad42)") (class "Default")
      (node (ref "U1") (pin "42") (pinfunction "RJ7/~{UB}_42") (pintype "passive+no_connect"))
    )
  )
)
